# New_Project_2023-10-24_16-38-30.net
KiCad netlist of a schematic drawn in EasyEDA Pro
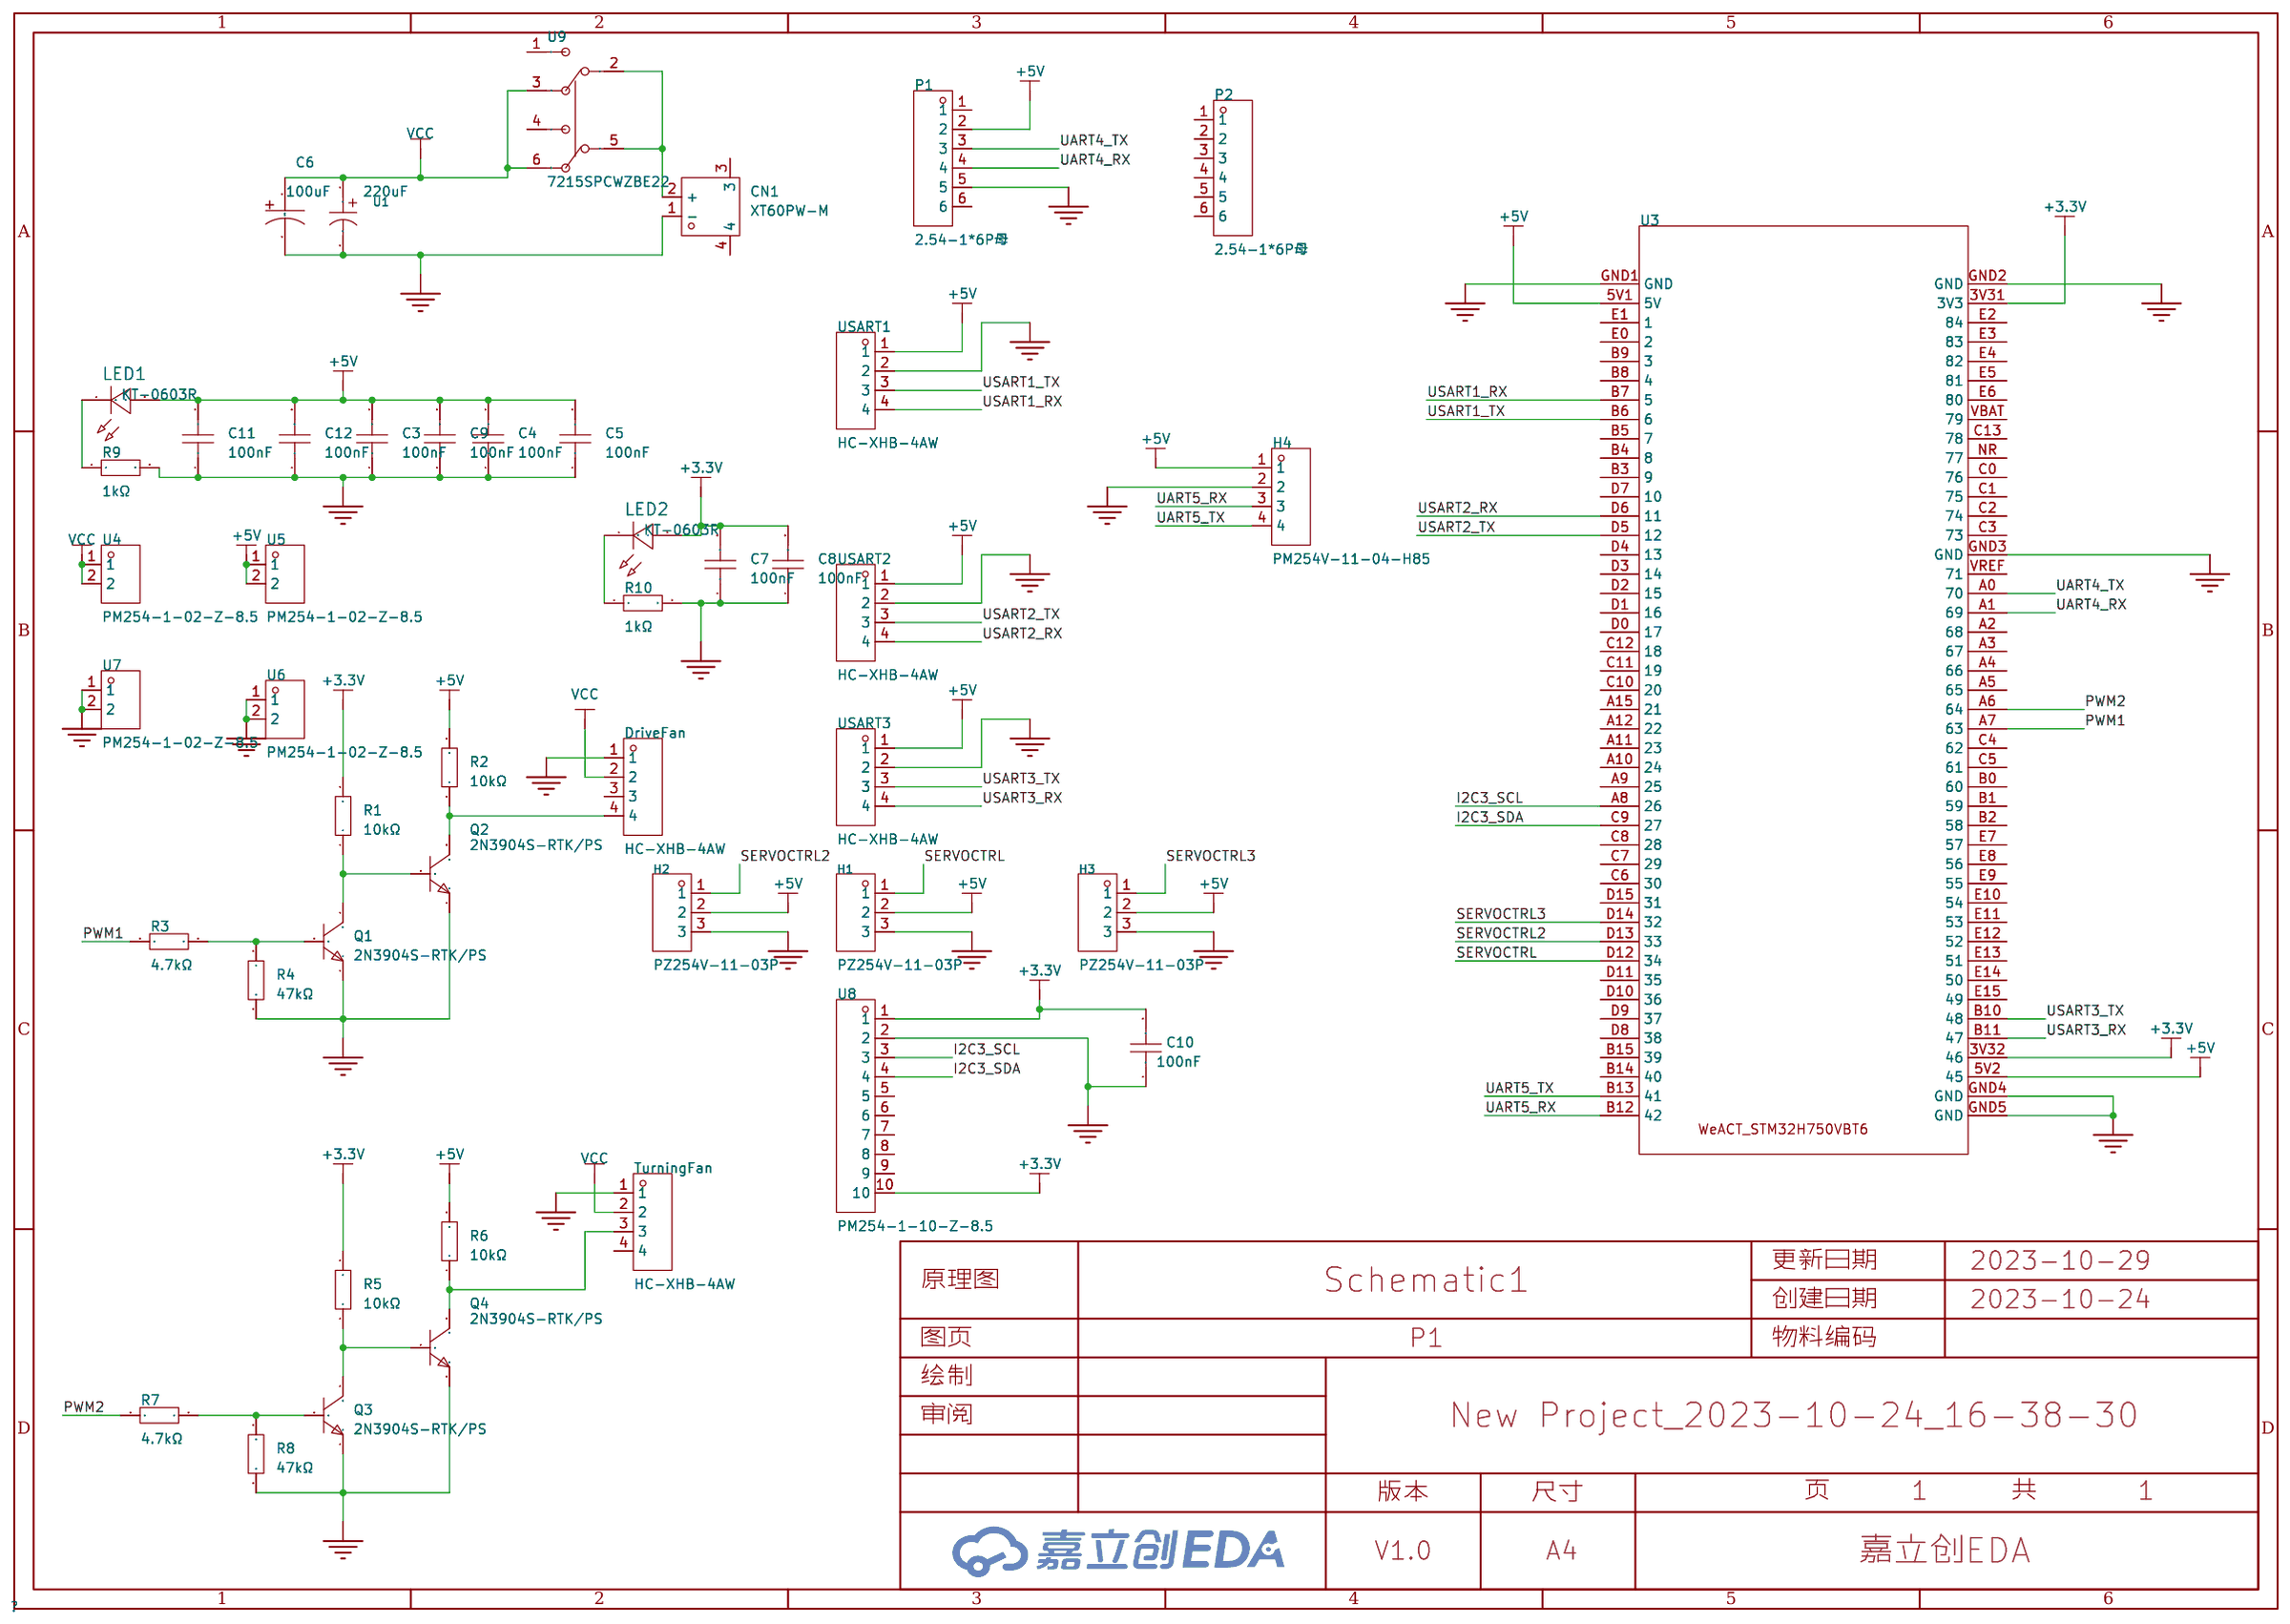
[diagram p0: schematic sheet]

(export (version "E")
  (design (tool "Eeschema 10.0.6"))
  (components
    (comp (ref "C3")
      (value "100nF")
      (footprint "easyedapro:C0603")
      (description "容值:100nF;精度:±10%;额定电压:50V;材质(温度系数):X7R;")
      (fields
        (field (name "Manufacturer Part") "CC0603KRX7R9BB104")
        (field (name "Manufacturer") "YAGEO(国巨)")
      )
      (libsource (lib "easyedapro") (part "CC0603KRX7R9BB104"))
    )
    (comp (ref "C4")
      (value "100nF")
      (footprint "easyedapro:C0603")
      (description "容值:100nF;精度:±10%;额定电压:50V;材质(温度系数):X7R;")
      (fields
        (field (name "Manufacturer Part") "CC0603KRX7R9BB104")
        (field (name "Manufacturer") "YAGEO(国巨)")
      )
      (libsource (lib "easyedapro") (part "CC0603KRX7R9BB104"))
    )
    (comp (ref "C5")
      (value "100nF")
      (footprint "easyedapro:C0603")
      (description "容值:100nF;精度:±10%;额定电压:50V;材质(温度系数):X7R;")
      (fields
        (field (name "Manufacturer Part") "CC0603KRX7R9BB104")
        (field (name "Manufacturer") "YAGEO(国巨)")
      )
      (libsource (lib "easyedapro") (part "CC0603KRX7R9BB104"))
    )
    (comp (ref "C6")
      (value "100uF")
      (footprint "easyedapro:CAP-SMD_BD6.3-L6.6-W6.6-RD")
      (description "容值:100uF;精度:±20%;额定电压:25V;纹波电流:-;等效串联电阻:-;")
      (fields (field (name "Manufacturer Part") "VZH101M1ETR-0607") (field (name "Manufacturer") "lelon(立隆)"))
      (libsource (lib "easyedapro") (part "VZH101M1ETR-0607"))
    )
    (comp (ref "C7")
      (value "100nF")
      (footprint "easyedapro:C0603")
      (description "容值:100nF;精度:±10%;额定电压:50V;材质(温度系数):X7R;")
      (fields
        (field (name "Manufacturer Part") "CC0603KRX7R9BB104")
        (field (name "Manufacturer") "YAGEO(国巨)")
      )
      (libsource (lib "easyedapro") (part "CC0603KRX7R9BB104"))
    )
    (comp (ref "C8")
      (value "100nF")
      (footprint "easyedapro:C0603")
      (description "容值:100nF;精度:±10%;额定电压:50V;材质(温度系数):X7R;")
      (fields
        (field (name "Manufacturer Part") "CC0603KRX7R9BB104")
        (field (name "Manufacturer") "YAGEO(国巨)")
      )
      (libsource (lib "easyedapro") (part "CC0603KRX7R9BB104"))
    )
    (comp (ref "C9")
      (value "100nF")
      (footprint "easyedapro:C0603")
      (description "容值:100nF;精度:±10%;额定电压:50V;材质(温度系数):X7R;")
      (fields
        (field (name "Manufacturer Part") "CC0603KRX7R9BB104")
        (field (name "Manufacturer") "YAGEO(国巨)")
      )
      (libsource (lib "easyedapro") (part "CC0603KRX7R9BB104"))
    )
    (comp (ref "C10")
      (value "100nF")
      (footprint "easyedapro:C0603")
      (description "容值:100nF;精度:±10%;额定电压:50V;材质(温度系数):X7R;")
      (fields
        (field (name "Manufacturer Part") "CC0603KRX7R9BB104")
        (field (name "Manufacturer") "YAGEO(国巨)")
      )
      (libsource (lib "easyedapro") (part "CC0603KRX7R9BB104"))
    )
    (comp (ref "C11")
      (value "100nF")
      (footprint "easyedapro:C0603")
      (description "容值:100nF;精度:±10%;额定电压:50V;材质(温度系数):X7R;")
      (fields
        (field (name "Manufacturer Part") "CC0603KRX7R9BB104")
        (field (name "Manufacturer") "YAGEO(国巨)")
      )
      (libsource (lib "easyedapro") (part "CC0603KRX7R9BB104"))
    )
    (comp (ref "C12")
      (value "100nF")
      (footprint "easyedapro:C0603")
      (description "容值:100nF;精度:±10%;额定电压:50V;材质(温度系数):X7R;")
      (fields
        (field (name "Manufacturer Part") "CC0603KRX7R9BB104")
        (field (name "Manufacturer") "YAGEO(国巨)")
      )
      (libsource (lib "easyedapro") (part "CC0603KRX7R9BB104"))
    )
    (comp (ref "CN1")
      (value "XT60PW-M")
      (footprint "easyedapro:CONN-TH_XT60PW-M")
      (description "模型锂电连接器")
      (fields (field (name "Manufacturer") "AMASS(艾迈斯)"))
      (libsource (lib "easyedapro") (part "XT60PW-M"))
    )
    (comp (ref "DriveFan")
      (value "HC-XHB-4AW")
      (footprint "easyedapro:CONN-TH_4P-P2.5_HCTL_HC-XHB-4AW")
      (description "参考系列:-;间距:2.5mm;插针结构:1x4P;排数:1;每排PIN数:4;行距:-;公母:公型插针;安装方式:弯插;额定电流:3A;工作温度范围:-25°C~+85°C;")
      (fields (field (name "Manufacturer") "HCTL(华灿天禄)"))
      (libsource (lib "easyedapro") (part "HC-XHB-4AW"))
    )
    (comp (ref "H1")
      (value "PZ254V-11-03P")
      (footprint "easyedapro:HDR-TH_3P-P2.54-V-M")
      (fields (field (name "Manufacturer") "XFCN(兴飞)"))
      (libsource (lib "easyedapro") (part "PZ254V-11-03P_C2937625"))
    )
    (comp (ref "H2")
      (value "PZ254V-11-03P")
      (footprint "easyedapro:HDR-TH_3P-P2.54-V-M")
      (fields (field (name "Manufacturer") "XFCN(兴飞)"))
      (libsource (lib "easyedapro") (part "PZ254V-11-03P_C2937625"))
    )
    (comp (ref "H3")
      (value "PZ254V-11-03P")
      (footprint "easyedapro:HDR-TH_3P-P2.54-V-M")
      (fields (field (name "Manufacturer") "XFCN(兴飞)"))
      (libsource (lib "easyedapro") (part "PZ254V-11-03P_C2937625"))
    )
    (comp (ref "H4")
      (value "PM254V-11-04-H85")
      (footprint "easyedapro:HDR-TH_4P-P2.54-V-F")
      (description "排数:单排;总孔位数:4P;间距:2.54mm;插孔结构:1x4P;行距:-;安装类型:直插;塑高:-;触头材质:黄铜;触头镀层:-;")
      (fields (field (name "Manufacturer") "XFCN(兴飞)"))
      (libsource (lib "easyedapro") (part "PM254V-11-04-H85"))
    )
    (comp (ref "LED1")
      (value "KT-0603R")
      (footprint "easyedapro:LED_0603")
      (fields (field (name "Manufacturer") "KENTO"))
      (libsource (lib "easyedapro") (part "LED_R"))
    )
    (comp (ref "LED2")
      (value "KT-0603R")
      (footprint "easyedapro:LED_0603")
      (fields (field (name "Manufacturer") "KENTO"))
      (libsource (lib "easyedapro") (part "LED_R"))
    )
    (comp (ref "P1")
      (value "2.54-1*6P母")
      (footprint "easyedapro:HDR-TH_6P-P2.54-V-F")
      (description "排数:单排;总孔位数:6P;间距:2.54mm;插孔结构:1x6P;行距:-;安装类型:直插;塑高:-;触头材质:-;触头镀层:-;")
      (fields (field (name "Manufacturer") "BOOMELE(博穆精密)"))
      (libsource (lib "easyedapro") (part "Header-Female-2.54_1x6"))
    )
    (comp (ref "P2")
      (value "2.54-1*6P母")
      (footprint "easyedapro:HDR-TH_6P-P2.54-V-F")
      (description "排数:单排;总孔位数:6P;间距:2.54mm;插孔结构:1x6P;行距:-;安装类型:直插;塑高:-;触头材质:-;触头镀层:-;")
      (fields (field (name "Manufacturer") "BOOMELE(博穆精密)"))
      (libsource (lib "easyedapro") (part "Header-Female-2.54_1x6"))
    )
    (comp (ref "Q1")
      (value "2N3904S-RTK/PS")
      (footprint "easyedapro:SOT-23-3_L2.9-W1.3-P1.90-LS2.4-TR")
      (description "晶体管类型:NPN;集射极击穿电压(Vceo):40V;集电极电流(Ic):200mA;功率(Pd):350mW;直流电流增益(hFE@Ic,Vce):100@10mA,1V;")
      (fields (field (name "Manufacturer") "KEC"))
      (libsource (lib "easyedapro") (part "2n3904S-RTK/PS_C18536"))
    )
    (comp (ref "Q2")
      (value "2N3904S-RTK/PS")
      (footprint "easyedapro:SOT-23-3_L2.9-W1.3-P1.90-LS2.4-TR")
      (description "晶体管类型:NPN;集射极击穿电压(Vceo):40V;集电极电流(Ic):200mA;功率(Pd):350mW;直流电流增益(hFE@Ic,Vce):100@10mA,1V;")
      (fields (field (name "Manufacturer") "KEC"))
      (libsource (lib "easyedapro") (part "2n3904S-RTK/PS_C18536"))
    )
    (comp (ref "Q3")
      (value "2N3904S-RTK/PS")
      (footprint "easyedapro:SOT-23-3_L2.9-W1.3-P1.90-LS2.4-TR")
      (description "晶体管类型:NPN;集射极击穿电压(Vceo):40V;集电极电流(Ic):200mA;功率(Pd):350mW;直流电流增益(hFE@Ic,Vce):100@10mA,1V;")
      (fields (field (name "Manufacturer") "KEC"))
      (libsource (lib "easyedapro") (part "2n3904S-RTK/PS_C18536"))
    )
    (comp (ref "Q4")
      (value "2N3904S-RTK/PS")
      (footprint "easyedapro:SOT-23-3_L2.9-W1.3-P1.90-LS2.4-TR")
      (description "晶体管类型:NPN;集射极击穿电压(Vceo):40V;集电极电流(Ic):200mA;功率(Pd):350mW;直流电流增益(hFE@Ic,Vce):100@10mA,1V;")
      (fields (field (name "Manufacturer") "KEC"))
      (libsource (lib "easyedapro") (part "2n3904S-RTK/PS_C18536"))
    )
    (comp (ref "R1")
      (value "10kΩ")
      (footprint "easyedapro:R0603")
      (fields
        (field (name "Manufacturer Part") "0603WAF1002T5E")
        (field (name "Manufacturer") "UNI-ROYAL(厚声)")
      )
      (libsource (lib "easyedapro") (part "电阻"))
    )
    (comp (ref "R2")
      (value "10kΩ")
      (footprint "easyedapro:R0603")
      (fields
        (field (name "Manufacturer Part") "0603WAF1002T5E")
        (field (name "Manufacturer") "UNI-ROYAL(厚声)")
      )
      (libsource (lib "easyedapro") (part "电阻"))
    )
    (comp (ref "R3")
      (value "4.7kΩ")
      (footprint "easyedapro:R0603")
      (fields
        (field (name "Manufacturer Part") "0603WAF4701T5E")
        (field (name "Manufacturer") "UNI-ROYAL(厚声)")
      )
      (libsource (lib "easyedapro") (part "电阻"))
    )
    (comp (ref "R4")
      (value "47kΩ")
      (footprint "easyedapro:R0603")
      (fields
        (field (name "Manufacturer Part") "0603WAF4702T5E")
        (field (name "Manufacturer") "UNI-ROYAL(厚声)")
      )
      (libsource (lib "easyedapro") (part "电阻"))
    )
    (comp (ref "R5")
      (value "10kΩ")
      (footprint "easyedapro:R0603")
      (fields
        (field (name "Manufacturer Part") "0603WAF1002T5E")
        (field (name "Manufacturer") "UNI-ROYAL(厚声)")
      )
      (libsource (lib "easyedapro") (part "电阻"))
    )
    (comp (ref "R6")
      (value "10kΩ")
      (footprint "easyedapro:R0603")
      (fields
        (field (name "Manufacturer Part") "0603WAF1002T5E")
        (field (name "Manufacturer") "UNI-ROYAL(厚声)")
      )
      (libsource (lib "easyedapro") (part "电阻"))
    )
    (comp (ref "R7")
      (value "4.7kΩ")
      (footprint "easyedapro:R0603")
      (fields
        (field (name "Manufacturer Part") "0603WAF4701T5E")
        (field (name "Manufacturer") "UNI-ROYAL(厚声)")
      )
      (libsource (lib "easyedapro") (part "电阻"))
    )
    (comp (ref "R8")
      (value "47kΩ")
      (footprint "easyedapro:R0603")
      (fields
        (field (name "Manufacturer Part") "0603WAF4702T5E")
        (field (name "Manufacturer") "UNI-ROYAL(厚声)")
      )
      (libsource (lib "easyedapro") (part "电阻"))
    )
    (comp (ref "R9")
      (value "1kΩ")
      (footprint "easyedapro:R0603")
      (fields
        (field (name "Manufacturer Part") "0603WAF1001T5E")
        (field (name "Manufacturer") "UNI-ROYAL(厚声)")
      )
      (libsource (lib "easyedapro") (part "电阻"))
    )
    (comp (ref "R10")
      (value "1kΩ")
      (footprint "easyedapro:R0603")
      (fields
        (field (name "Manufacturer Part") "0603WAF1001T5E")
        (field (name "Manufacturer") "UNI-ROYAL(厚声)")
      )
      (libsource (lib "easyedapro") (part "电阻"))
    )
    (comp (ref "TurningFan")
      (value "HC-XHB-4AW")
      (footprint "easyedapro:CONN-TH_4P-P2.5_HCTL_HC-XHB-4AW")
      (description "参考系列:-;间距:2.5mm;插针结构:1x4P;排数:1;每排PIN数:4;行距:-;公母:公型插针;安装方式:弯插;额定电流:3A;工作温度范围:-25°C~+85°C;")
      (fields (field (name "Manufacturer") "HCTL(华灿天禄)"))
      (libsource (lib "easyedapro") (part "HC-XHB-4AW"))
    )
    (comp (ref "U1")
      (value "220uF")
      (footprint "easyedapro:CAP-SMD_BD6.3-L6.6-W6.6-LS7.2-FD")
      (description "容值:220uF;精度:±20%;额定电压:25V;纹波电流:165mA@120Hz;等效串联电阻:-;")
      (fields (field (name "Manufacturer Part") "RST220UF25V019") (field (name "Manufacturer") "KNSCHA(科尼盛)"))
      (libsource (lib "easyedapro") (part "RST220UF25V019"))
    )
    (comp (ref "U3")
      (value "~")
      (footprint "easyedapro:WeAct_STM32H750VBT6核心板")
      (libsource (lib "easyedapro") (part "STM32H750VBT6"))
    )
    (comp (ref "U4")
      (value "PM254-1-02-Z-8.5")
      (footprint "easyedapro:HDR-TH_2P-P2.54-V-F")
      (fields (field (name "Manufacturer") "HCTL(华灿天禄)"))
      (libsource (lib "easyedapro") (part "PM254-1-02-Z-8.5"))
    )
    (comp (ref "U5")
      (value "PM254-1-02-Z-8.5")
      (footprint "easyedapro:HDR-TH_2P-P2.54-V-F")
      (fields (field (name "Manufacturer") "HCTL(华灿天禄)"))
      (libsource (lib "easyedapro") (part "PM254-1-02-Z-8.5"))
    )
    (comp (ref "U6")
      (value "PM254-1-02-Z-8.5")
      (footprint "easyedapro:HDR-TH_2P-P2.54-V-F")
      (fields (field (name "Manufacturer") "HCTL(华灿天禄)"))
      (libsource (lib "easyedapro") (part "PM254-1-02-Z-8.5"))
    )
    (comp (ref "U7")
      (value "PM254-1-02-Z-8.5")
      (footprint "easyedapro:HDR-TH_2P-P2.54-V-F")
      (fields (field (name "Manufacturer") "HCTL(华灿天禄)"))
      (libsource (lib "easyedapro") (part "PM254-1-02-Z-8.5"))
    )
    (comp (ref "U8")
      (value "PM254-1-10-Z-8.5")
      (footprint "easyedapro:HDR-TH_10P-P2.54-V-F")
      (fields (field (name "Manufacturer") "HCTL(华灿天禄)"))
      (libsource (lib "easyedapro") (part "PM254-1-10-Z-8.5"))
    )
    (comp (ref "U9")
      (value "7215SPCWZBE22")
      (footprint "easyedapro:SW-TH_6P-L12.7-W11.4-P4.70-LS4.8")
      (fields (field (name "Manufacturer") "C&amp;K"))
      (libsource (lib "easyedapro") (part "7215SPCWZBE22"))
    )
    (comp (ref "USART1")
      (value "HC-XHB-4AW")
      (footprint "easyedapro:CONN-TH_4P-P2.5_HCTL_HC-XHB-4AW")
      (description "参考系列:-;间距:2.5mm;插针结构:1x4P;排数:1;每排PIN数:4;行距:-;公母:公型插针;安装方式:弯插;额定电流:3A;工作温度范围:-25°C~+85°C;")
      (fields (field (name "Manufacturer") "HCTL(华灿天禄)"))
      (libsource (lib "easyedapro") (part "HC-XHB-4AW"))
    )
    (comp (ref "USART2")
      (value "HC-XHB-4AW")
      (footprint "easyedapro:CONN-TH_4P-P2.5_HCTL_HC-XHB-4AW")
      (description "参考系列:-;间距:2.5mm;插针结构:1x4P;排数:1;每排PIN数:4;行距:-;公母:公型插针;安装方式:弯插;额定电流:3A;工作温度范围:-25°C~+85°C;")
      (fields (field (name "Manufacturer") "HCTL(华灿天禄)"))
      (libsource (lib "easyedapro") (part "HC-XHB-4AW"))
    )
    (comp (ref "USART3")
      (value "HC-XHB-4AW")
      (footprint "easyedapro:CONN-TH_4P-P2.5_HCTL_HC-XHB-4AW")
      (description "参考系列:-;间距:2.5mm;插针结构:1x4P;排数:1;每排PIN数:4;行距:-;公母:公型插针;安装方式:弯插;额定电流:3A;工作温度范围:-25°C~+85°C;")
      (fields (field (name "Manufacturer") "HCTL(华灿天禄)"))
      (libsource (lib "easyedapro") (part "HC-XHB-4AW"))
    )
  )
  (nets
    (net (code "1") (name "+3.3V") (class "Default")
      (node (ref "C10") (pin "2") (pinfunction "2_2") (pintype "input"))
      (node (ref "C7") (pin "2") (pinfunction "2_2") (pintype "input"))
      (node (ref "C8") (pin "2") (pinfunction "2_2") (pintype "input"))
      (node (ref "LED2") (pin "2") (pinfunction "A_2") (pintype "input"))
      (node (ref "R1") (pin "2") (pinfunction "2_2") (pintype "input"))
      (node (ref "R5") (pin "2") (pinfunction "2_2") (pintype "input"))
      (node (ref "U3") (pin "3V31") (pinfunction "3V3_3V31") (pintype "input"))
      (node (ref "U3") (pin "3V32") (pinfunction "46_3V32") (pintype "input"))
      (node (ref "U8") (pin "1") (pinfunction "1_1") (pintype "unspecified"))
      (node (ref "U8") (pin "10") (pinfunction "10_10") (pintype "unspecified"))
    )
    (net (code "2") (name "+5V") (class "Default")
      (node (ref "C11") (pin "2") (pinfunction "2_2") (pintype "input"))
      (node (ref "C12") (pin "2") (pinfunction "2_2") (pintype "input"))
      (node (ref "C3") (pin "2") (pinfunction "2_2") (pintype "input"))
      (node (ref "C4") (pin "2") (pinfunction "2_2") (pintype "input"))
      (node (ref "C5") (pin "2") (pinfunction "2_2") (pintype "input"))
      (node (ref "C9") (pin "2") (pinfunction "2_2") (pintype "input"))
      (node (ref "H1") (pin "2") (pinfunction "2_2") (pintype "input"))
      (node (ref "H2") (pin "2") (pinfunction "2_2") (pintype "input"))
      (node (ref "H3") (pin "2") (pinfunction "2_2") (pintype "input"))
      (node (ref "H4") (pin "1") (pinfunction "1_1") (pintype "unspecified"))
      (node (ref "LED1") (pin "2") (pinfunction "A_2") (pintype "input"))
      (node (ref "P1") (pin "2") (pinfunction "2_2") (pintype "unspecified"))
      (node (ref "R2") (pin "2") (pinfunction "2_2") (pintype "input"))
      (node (ref "R6") (pin "2") (pinfunction "2_2") (pintype "input"))
      (node (ref "U3") (pin "5V1") (pinfunction "5V_5V1") (pintype "input"))
      (node (ref "U3") (pin "5V2") (pinfunction "45_5V2") (pintype "input"))
      (node (ref "U5") (pin "1") (pinfunction "1_1") (pintype "unspecified"))
      (node (ref "U5") (pin "2") (pinfunction "2_2") (pintype "unspecified"))
      (node (ref "USART1") (pin "1") (pinfunction "1_1") (pintype "input"))
      (node (ref "USART2") (pin "1") (pinfunction "1_1") (pintype "input"))
      (node (ref "USART3") (pin "1") (pinfunction "1_1") (pintype "input"))
    )
    (net (code "3") (name "/I2C3_SCL") (class "Default")
      (node (ref "U3") (pin "A8") (pinfunction "26_A8") (pintype "input"))
      (node (ref "U8") (pin "3") (pinfunction "3_3") (pintype "unspecified"))
    )
    (net (code "4") (name "/I2C3_SDA") (class "Default")
      (node (ref "U3") (pin "C9") (pinfunction "27_C9") (pintype "input"))
      (node (ref "U8") (pin "4") (pinfunction "4_4") (pintype "unspecified"))
    )
    (net (code "5") (name "/PWM1") (class "Default")
      (node (ref "R3") (pin "2") (pinfunction "2_2") (pintype "input"))
      (node (ref "U3") (pin "A7") (pinfunction "63_A7") (pintype "input"))
    )
    (net (code "6") (name "/PWM2") (class "Default")
      (node (ref "R7") (pin "2") (pinfunction "2_2") (pintype "input"))
      (node (ref "U3") (pin "A6") (pinfunction "64_A6") (pintype "input"))
    )
    (net (code "7") (name "/SERVOCTRL") (class "Default")
      (node (ref "H1") (pin "1") (pinfunction "1_1") (pintype "input"))
      (node (ref "U3") (pin "D12") (pinfunction "34_D12") (pintype "input"))
    )
    (net (code "8") (name "/SERVOCTRL2") (class "Default")
      (node (ref "H2") (pin "1") (pinfunction "1_1") (pintype "input"))
      (node (ref "U3") (pin "D13") (pinfunction "33_D13") (pintype "input"))
    )
    (net (code "9") (name "/SERVOCTRL3") (class "Default")
      (node (ref "H3") (pin "1") (pinfunction "1_1") (pintype "input"))
      (node (ref "U3") (pin "D14") (pinfunction "32_D14") (pintype "input"))
    )
    (net (code "10") (name "/UART4_RX") (class "Default")
      (node (ref "P1") (pin "4") (pinfunction "4_4") (pintype "unspecified"))
      (node (ref "U3") (pin "A1") (pinfunction "69_A1") (pintype "input"))
    )
    (net (code "11") (name "/UART4_TX") (class "Default")
      (node (ref "P1") (pin "3") (pinfunction "3_3") (pintype "unspecified"))
      (node (ref "U3") (pin "A0") (pinfunction "70_A0") (pintype "input"))
    )
    (net (code "12") (name "/UART5_RX") (class "Default")
      (node (ref "H4") (pin "3") (pinfunction "3_3") (pintype "unspecified"))
      (node (ref "U3") (pin "B12") (pinfunction "42_B12") (pintype "input"))
    )
    (net (code "13") (name "/UART5_TX") (class "Default")
      (node (ref "H4") (pin "4") (pinfunction "4_4") (pintype "unspecified"))
      (node (ref "U3") (pin "B13") (pinfunction "41_B13") (pintype "input"))
    )
    (net (code "14") (name "/USART1_RX") (class "Default")
      (node (ref "U3") (pin "B7") (pinfunction "5_B7") (pintype "input"))
      (node (ref "USART1") (pin "4") (pinfunction "4_4") (pintype "input"))
    )
    (net (code "15") (name "/USART1_TX") (class "Default")
      (node (ref "U3") (pin "B6") (pinfunction "6_B6") (pintype "input"))
      (node (ref "USART1") (pin "3") (pinfunction "3_3") (pintype "input"))
    )
    (net (code "16") (name "/USART2_RX") (class "Default")
      (node (ref "U3") (pin "D6") (pinfunction "11_D6") (pintype "input"))
      (node (ref "USART2") (pin "4") (pinfunction "4_4") (pintype "input"))
    )
    (net (code "17") (name "/USART2_TX") (class "Default")
      (node (ref "U3") (pin "D5") (pinfunction "12_D5") (pintype "input"))
      (node (ref "USART2") (pin "3") (pinfunction "3_3") (pintype "input"))
    )
    (net (code "18") (name "/USART3_RX") (class "Default")
      (node (ref "U3") (pin "B11") (pinfunction "47_B11") (pintype "input"))
      (node (ref "USART3") (pin "4") (pinfunction "4_4") (pintype "input"))
    )
    (net (code "19") (name "/USART3_TX") (class "Default")
      (node (ref "U3") (pin "B10") (pinfunction "48_B10") (pintype "input"))
      (node (ref "USART3") (pin "3") (pinfunction "3_3") (pintype "input"))
    )
    (net (code "20") (name "GND") (class "Default")
      (node (ref "C10") (pin "1") (pinfunction "1_1") (pintype "input"))
      (node (ref "C11") (pin "1") (pinfunction "1_1") (pintype "input"))
      (node (ref "C12") (pin "1") (pinfunction "1_1") (pintype "input"))
      (node (ref "C3") (pin "1") (pinfunction "1_1") (pintype "input"))
      (node (ref "C4") (pin "1") (pinfunction "1_1") (pintype "input"))
      (node (ref "C5") (pin "1") (pinfunction "1_1") (pintype "input"))
      (node (ref "C6") (pin "2") (pinfunction "2_2") (pintype "input"))
      (node (ref "C7") (pin "1") (pinfunction "1_1") (pintype "input"))
      (node (ref "C8") (pin "1") (pinfunction "1_1") (pintype "input"))
      (node (ref "C9") (pin "1") (pinfunction "1_1") (pintype "input"))
      (node (ref "CN1") (pin "1") (pinfunction "-_1") (pintype "input"))
      (node (ref "DriveFan") (pin "1") (pinfunction "1_1") (pintype "input"))
      (node (ref "H1") (pin "3") (pinfunction "3_3") (pintype "input"))
      (node (ref "H2") (pin "3") (pinfunction "3_3") (pintype "input"))
      (node (ref "H3") (pin "3") (pinfunction "3_3") (pintype "input"))
      (node (ref "H4") (pin "2") (pinfunction "2_2") (pintype "unspecified"))
      (node (ref "P1") (pin "5") (pinfunction "5_5") (pintype "unspecified"))
      (node (ref "Q1") (pin "1") (pinfunction "E_1") (pintype "input"))
      (node (ref "Q2") (pin "1") (pinfunction "E_1") (pintype "input"))
      (node (ref "Q3") (pin "1") (pinfunction "E_1") (pintype "input"))
      (node (ref "Q4") (pin "1") (pinfunction "E_1") (pintype "input"))
      (node (ref "R10") (pin "2") (pinfunction "2_2") (pintype "input"))
      (node (ref "R4") (pin "2") (pinfunction "2_2") (pintype "input"))
      (node (ref "R8") (pin "2") (pinfunction "2_2") (pintype "input"))
      (node (ref "R9") (pin "2") (pinfunction "2_2") (pintype "input"))
      (node (ref "TurningFan") (pin "1") (pinfunction "1_1") (pintype "input"))
      (node (ref "U1") (pin "2") (pinfunction "2_2") (pintype "input"))
      (node (ref "U3") (pin "GND1") (pinfunction "GND_GND1") (pintype "input"))
      (node (ref "U3") (pin "GND2") (pinfunction "GND_GND2") (pintype "input"))
      (node (ref "U3") (pin "GND3") (pinfunction "GND_GND3") (pintype "input"))
      (node (ref "U3") (pin "GND4") (pinfunction "GND_GND4") (pintype "input"))
      (node (ref "U3") (pin "GND5") (pinfunction "GND_GND5") (pintype "input"))
      (node (ref "U6") (pin "1") (pinfunction "1_1") (pintype "unspecified"))
      (node (ref "U6") (pin "2") (pinfunction "2_2") (pintype "unspecified"))
      (node (ref "U7") (pin "1") (pinfunction "1_1") (pintype "unspecified"))
      (node (ref "U7") (pin "2") (pinfunction "2_2") (pintype "unspecified"))
      (node (ref "U8") (pin "2") (pinfunction "2_2") (pintype "unspecified"))
      (node (ref "USART1") (pin "2") (pinfunction "2_2") (pintype "input"))
      (node (ref "USART2") (pin "2") (pinfunction "2_2") (pintype "input"))
      (node (ref "USART3") (pin "2") (pinfunction "2_2") (pintype "input"))
    )
    (net (code "21") (name "Net-(CN1-+)") (class "Default")
      (node (ref "CN1") (pin "2") (pinfunction "+_2") (pintype "input"))
      (node (ref "U9") (pin "2") (pinfunction "2_2") (pintype "input"))
      (node (ref "U9") (pin "5") (pinfunction "5_5") (pintype "input"))
    )
    (net (code "22") (name "Net-(LED1-C)") (class "Default")
      (node (ref "LED1") (pin "1") (pinfunction "C_1") (pintype "input"))
      (node (ref "R9") (pin "1") (pinfunction "1_1") (pintype "input"))
    )
    (net (code "23") (name "Net-(LED2-C)") (class "Default")
      (node (ref "LED2") (pin "1") (pinfunction "C_1") (pintype "input"))
      (node (ref "R10") (pin "1") (pinfunction "1_1") (pintype "input"))
    )
    (net (code "24") (name "Net-(Q1-B)") (class "Default")
      (node (ref "Q1") (pin "2") (pinfunction "B_2") (pintype "input"))
      (node (ref "R3") (pin "1") (pinfunction "1_1") (pintype "input"))
      (node (ref "R4") (pin "1") (pinfunction "1_1") (pintype "input"))
    )
    (net (code "25") (name "Net-(Q1-C)") (class "Default")
      (node (ref "Q1") (pin "3") (pinfunction "C_3") (pintype "input"))
      (node (ref "Q2") (pin "2") (pinfunction "B_2") (pintype "input"))
      (node (ref "R1") (pin "1") (pinfunction "1_1") (pintype "input"))
    )
    (net (code "26") (name "Net-(Q2-C)") (class "Default")
      (node (ref "DriveFan") (pin "4") (pinfunction "4_4") (pintype "input"))
      (node (ref "Q2") (pin "3") (pinfunction "C_3") (pintype "input"))
      (node (ref "R2") (pin "1") (pinfunction "1_1") (pintype "input"))
    )
    (net (code "27") (name "Net-(Q3-B)") (class "Default")
      (node (ref "Q3") (pin "2") (pinfunction "B_2") (pintype "input"))
      (node (ref "R7") (pin "1") (pinfunction "1_1") (pintype "input"))
      (node (ref "R8") (pin "1") (pinfunction "1_1") (pintype "input"))
    )
    (net (code "28") (name "Net-(Q3-C)") (class "Default")
      (node (ref "Q3") (pin "3") (pinfunction "C_3") (pintype "input"))
      (node (ref "Q4") (pin "2") (pinfunction "B_2") (pintype "input"))
      (node (ref "R5") (pin "1") (pinfunction "1_1") (pintype "input"))
    )
    (net (code "29") (name "Net-(Q4-C)") (class "Default")
      (node (ref "Q4") (pin "3") (pinfunction "C_3") (pintype "input"))
      (node (ref "R6") (pin "1") (pinfunction "1_1") (pintype "input"))
      (node (ref "TurningFan") (pin "3") (pinfunction "3_3") (pintype "input"))
    )
    (net (code "30") (name "VCC") (class "Default")
      (node (ref "C6") (pin "1") (pinfunction "1_1") (pintype "input"))
      (node (ref "DriveFan") (pin "2") (pinfunction "2_2") (pintype "input"))
      (node (ref "TurningFan") (pin "2") (pinfunction "2_2") (pintype "input"))
      (node (ref "U1") (pin "1") (pinfunction "1_1") (pintype "input"))
      (node (ref "U4") (pin "1") (pinfunction "1_1") (pintype "unspecified"))
      (node (ref "U4") (pin "2") (pinfunction "2_2") (pintype "unspecified"))
      (node (ref "U9") (pin "3") (pinfunction "3_3") (pintype "input"))
      (node (ref "U9") (pin "6") (pinfunction "6_6") (pintype "input"))
    )
    (net (code "31") (name "unconnected-(CN1-Pad3)") (class "Default")
      (node (ref "CN1") (pin "3") (pinfunction "3_3") (pintype "input"))
    )
    (net (code "32") (name "unconnected-(CN1-Pad4)") (class "Default")
      (node (ref "CN1") (pin "4") (pinfunction "4_4") (pintype "input"))
    )
    (net (code "33") (name "unconnected-(DriveFan-Pad3)") (class "Default")
      (node (ref "DriveFan") (pin "3") (pinfunction "3_3") (pintype "input"))
    )
    (net (code "34") (name "unconnected-(P1-Pad1)") (class "Default")
      (node (ref "P1") (pin "1") (pinfunction "1_1") (pintype "unspecified"))
    )
    (net (code "35") (name "unconnected-(P1-Pad6)") (class "Default")
      (node (ref "P1") (pin "6") (pinfunction "6_6") (pintype "unspecified"))
    )
    (net (code "36") (name "unconnected-(P2-Pad1)") (class "Default")
      (node (ref "P2") (pin "1") (pinfunction "1_1") (pintype "unspecified"))
    )
    (net (code "37") (name "unconnected-(P2-Pad2)") (class "Default")
      (node (ref "P2") (pin "2") (pinfunction "2_2") (pintype "unspecified"))
    )
    (net (code "38") (name "unconnected-(P2-Pad3)") (class "Default")
      (node (ref "P2") (pin "3") (pinfunction "3_3") (pintype "unspecified"))
    )
    (net (code "39") (name "unconnected-(P2-Pad4)") (class "Default")
      (node (ref "P2") (pin "4") (pinfunction "4_4") (pintype "unspecified"))
    )
    (net (code "40") (name "unconnected-(P2-Pad5)") (class "Default")
      (node (ref "P2") (pin "5") (pinfunction "5_5") (pintype "unspecified"))
    )
    (net (code "41") (name "unconnected-(P2-Pad6)") (class "Default")
      (node (ref "P2") (pin "6") (pinfunction "6_6") (pintype "unspecified"))
    )
    (net (code "42") (name "unconnected-(TurningFan-Pad4)") (class "Default")
      (node (ref "TurningFan") (pin "4") (pinfunction "4_4") (pintype "input"))
    )
    (net (code "43") (name "unconnected-(U3-1-PadE1)") (class "Default")
      (node (ref "U3") (pin "E1") (pinfunction "1_E1") (pintype "input"))
    )
    (net (code "44") (name "unconnected-(U3-2-PadE0)") (class "Default")
      (node (ref "U3") (pin "E0") (pinfunction "2_E0") (pintype "input"))
    )
    (net (code "45") (name "unconnected-(U3-3-PadB9)") (class "Default")
      (node (ref "U3") (pin "B9") (pinfunction "3_B9") (pintype "input"))
    )
    (net (code "46") (name "unconnected-(U3-4-PadB8)") (class "Default")
      (node (ref "U3") (pin "B8") (pinfunction "4_B8") (pintype "input"))
    )
    (net (code "47") (name "unconnected-(U3-7-PadB5)") (class "Default")
      (node (ref "U3") (pin "B5") (pinfunction "7_B5") (pintype "input"))
    )
    (net (code "48") (name "unconnected-(U3-8-PadB4)") (class "Default")
      (node (ref "U3") (pin "B4") (pinfunction "8_B4") (pintype "input"))
    )
    (net (code "49") (name "unconnected-(U3-9-PadB3)") (class "Default")
      (node (ref "U3") (pin "B3") (pinfunction "9_B3") (pintype "input"))
    )
    (net (code "50") (name "unconnected-(U3-10-PadD7)") (class "Default")
      (node (ref "U3") (pin "D7") (pinfunction "10_D7") (pintype "input"))
    )
    (net (code "51") (name "unconnected-(U3-13-PadD4)") (class "Default")
      (node (ref "U3") (pin "D4") (pinfunction "13_D4") (pintype "input"))
    )
    (net (code "52") (name "unconnected-(U3-14-PadD3)") (class "Default")
      (node (ref "U3") (pin "D3") (pinfunction "14_D3") (pintype "input"))
    )
    (net (code "53") (name "unconnected-(U3-15-PadD2)") (class "Default")
      (node (ref "U3") (pin "D2") (pinfunction "15_D2") (pintype "input"))
    )
    (net (code "54") (name "unconnected-(U3-16-PadD1)") (class "Default")
      (node (ref "U3") (pin "D1") (pinfunction "16_D1") (pintype "input"))
    )
    (net (code "55") (name "unconnected-(U3-17-PadD0)") (class "Default")
      (node (ref "U3") (pin "D0") (pinfunction "17_D0") (pintype "input"))
    )
    (net (code "56") (name "unconnected-(U3-18-PadC12)") (class "Default")
      (node (ref "U3") (pin "C12") (pinfunction "18_C12") (pintype "input"))
    )
    (net (code "57") (name "unconnected-(U3-19-PadC11)") (class "Default")
      (node (ref "U3") (pin "C11") (pinfunction "19_C11") (pintype "input"))
    )
    (net (code "58") (name "unconnected-(U3-20-PadC10)") (class "Default")
      (node (ref "U3") (pin "C10") (pinfunction "20_C10") (pintype "input"))
    )
    (net (code "59") (name "unconnected-(U3-21-PadA15)") (class "Default")
      (node (ref "U3") (pin "A15") (pinfunction "21_A15") (pintype "input"))
    )
    (net (code "60") (name "unconnected-(U3-22-PadA12)") (class "Default")
      (node (ref "U3") (pin "A12") (pinfunction "22_A12") (pintype "input"))
    )
    (net (code "61") (name "unconnected-(U3-23-PadA11)") (class "Default")
      (node (ref "U3") (pin "A11") (pinfunction "23_A11") (pintype "input"))
    )
    (net (code "62") (name "unconnected-(U3-24-PadA10)") (class "Default")
      (node (ref "U3") (pin "A10") (pinfunction "24_A10") (pintype "input"))
    )
    (net (code "63") (name "unconnected-(U3-25-PadA9)") (class "Default")
      (node (ref "U3") (pin "A9") (pinfunction "25_A9") (pintype "input"))
    )
    (net (code "64") (name "unconnected-(U3-28-PadC8)") (class "Default")
      (node (ref "U3") (pin "C8") (pinfunction "28_C8") (pintype "input"))
    )
    (net (code "65") (name "unconnected-(U3-29-PadC7)") (class "Default")
      (node (ref "U3") (pin "C7") (pinfunction "29_C7") (pintype "input"))
    )
    (net (code "66") (name "unconnected-(U3-30-PadC6)") (class "Default")
      (node (ref "U3") (pin "C6") (pinfunction "30_C6") (pintype "input"))
    )
    (net (code "67") (name "unconnected-(U3-31-PadD15)") (class "Default")
      (node (ref "U3") (pin "D15") (pinfunction "31_D15") (pintype "input"))
    )
    (net (code "68") (name "unconnected-(U3-35-PadD11)") (class "Default")
      (node (ref "U3") (pin "D11") (pinfunction "35_D11") (pintype "input"))
    )
    (net (code "69") (name "unconnected-(U3-36-PadD10)") (class "Default")
      (node (ref "U3") (pin "D10") (pinfunction "36_D10") (pintype "input"))
    )
    (net (code "70") (name "unconnected-(U3-37-PadD9)") (class "Default")
      (node (ref "U3") (pin "D9") (pinfunction "37_D9") (pintype "input"))
    )
    (net (code "71") (name "unconnected-(U3-38-PadD8)") (class "Default")
      (node (ref "U3") (pin "D8") (pinfunction "38_D8") (pintype "input"))
    )
    (net (code "72") (name "unconnected-(U3-39-PadB15)") (class "Default")
      (node (ref "U3") (pin "B15") (pinfunction "39_B15") (pintype "input"))
    )
    (net (code "73") (name "unconnected-(U3-40-PadB14)") (class "Default")
      (node (ref "U3") (pin "B14") (pinfunction "40_B14") (pintype "input"))
    )
    (net (code "74") (name "unconnected-(U3-49-PadE15)") (class "Default")
      (node (ref "U3") (pin "E15") (pinfunction "49_E15") (pintype "input"))
    )
    (net (code "75") (name "unconnected-(U3-50-PadE14)") (class "Default")
      (node (ref "U3") (pin "E14") (pinfunction "50_E14") (pintype "input"))
    )
    (net (code "76") (name "unconnected-(U3-51-PadE13)") (class "Default")
      (node (ref "U3") (pin "E13") (pinfunction "51_E13") (pintype "input"))
    )
    (net (code "77") (name "unconnected-(U3-52-PadE12)") (class "Default")
      (node (ref "U3") (pin "E12") (pinfunction "52_E12") (pintype "input"))
    )
    (net (code "78") (name "unconnected-(U3-53-PadE11)") (class "Default")
      (node (ref "U3") (pin "E11") (pinfunction "53_E11") (pintype "input"))
    )
    (net (code "79") (name "unconnected-(U3-54-PadE10)") (class "Default")
      (node (ref "U3") (pin "E10") (pinfunction "54_E10") (pintype "input"))
    )
    (net (code "80") (name "unconnected-(U3-55-PadE9)") (class "Default")
      (node (ref "U3") (pin "E9") (pinfunction "55_E9") (pintype "input"))
    )
    (net (code "81") (name "unconnected-(U3-56-PadE8)") (class "Default")
      (node (ref "U3") (pin "E8") (pinfunction "56_E8") (pintype "input"))
    )
    (net (code "82") (name "unconnected-(U3-57-PadE7)") (class "Default")
      (node (ref "U3") (pin "E7") (pinfunction "57_E7") (pintype "input"))
    )
    (net (code "83") (name "unconnected-(U3-58-PadB2)") (class "Default")
      (node (ref "U3") (pin "B2") (pinfunction "58_B2") (pintype "input"))
    )
    (net (code "84") (name "unconnected-(U3-59-PadB1)") (class "Default")
      (node (ref "U3") (pin "B1") (pinfunction "59_B1") (pintype "input"))
    )
    (net (code "85") (name "unconnected-(U3-60-PadB0)") (class "Default")
      (node (ref "U3") (pin "B0") (pinfunction "60_B0") (pintype "input"))
    )
    (net (code "86") (name "unconnected-(U3-61-PadC5)") (class "Default")
      (node (ref "U3") (pin "C5") (pinfunction "61_C5") (pintype "input"))
    )
    (net (code "87") (name "unconnected-(U3-62-PadC4)") (class "Default")
      (node (ref "U3") (pin "C4") (pinfunction "62_C4") (pintype "input"))
    )
    (net (code "88") (name "unconnected-(U3-65-PadA5)") (class "Default")
      (node (ref "U3") (pin "A5") (pinfunction "65_A5") (pintype "input"))
    )
    (net (code "89") (name "unconnected-(U3-66-PadA4)") (class "Default")
      (node (ref "U3") (pin "A4") (pinfunction "66_A4") (pintype "input"))
    )
    (net (code "90") (name "unconnected-(U3-67-PadA3)") (class "Default")
      (node (ref "U3") (pin "A3") (pinfunction "67_A3") (pintype "input"))
    )
    (net (code "91") (name "unconnected-(U3-68-PadA2)") (class "Default")
      (node (ref "U3") (pin "A2") (pinfunction "68_A2") (pintype "input"))
    )
    (net (code "92") (name "unconnected-(U3-71-PadVREF)") (class "Default")
      (node (ref "U3") (pin "VREF") (pinfunction "71_VREF") (pintype "input"))
    )
    (net (code "93") (name "unconnected-(U3-73-PadC3)") (class "Default")
      (node (ref "U3") (pin "C3") (pinfunction "73_C3") (pintype "input"))
    )
    (net (code "94") (name "unconnected-(U3-74-PadC2)") (class "Default")
      (node (ref "U3") (pin "C2") (pinfunction "74_C2") (pintype "input"))
    )
    (net (code "95") (name "unconnected-(U3-75-PadC1)") (class "Default")
      (node (ref "U3") (pin "C1") (pinfunction "75_C1") (pintype "input"))
    )
    (net (code "96") (name "unconnected-(U3-76-PadC0)") (class "Default")
      (node (ref "U3") (pin "C0") (pinfunction "76_C0") (pintype "input"))
    )
    (net (code "97") (name "unconnected-(U3-77-PadNR)") (class "Default")
      (node (ref "U3") (pin "NR") (pinfunction "77_NR") (pintype "input"))
    )
    (net (code "98") (name "unconnected-(U3-78-PadC13)") (class "Default")
      (node (ref "U3") (pin "C13") (pinfunction "78_C13") (pintype "input"))
    )
    (net (code "99") (name "unconnected-(U3-79-PadVBAT)") (class "Default")
      (node (ref "U3") (pin "VBAT") (pinfunction "79_VBAT") (pintype "input"))
    )
    (net (code "100") (name "unconnected-(U3-80-PadE6)") (class "Default")
      (node (ref "U3") (pin "E6") (pinfunction "80_E6") (pintype "input"))
    )
    (net (code "101") (name "unconnected-(U3-81-PadE5)") (class "Default")
      (node (ref "U3") (pin "E5") (pinfunction "81_E5") (pintype "input"))
    )
    (net (code "102") (name "unconnected-(U3-82-PadE4)") (class "Default")
      (node (ref "U3") (pin "E4") (pinfunction "82_E4") (pintype "input"))
    )
    (net (code "103") (name "unconnected-(U3-83-PadE3)") (class "Default")
      (node (ref "U3") (pin "E3") (pinfunction "83_E3") (pintype "input"))
    )
    (net (code "104") (name "unconnected-(U3-84-PadE2)") (class "Default")
      (node (ref "U3") (pin "E2") (pinfunction "84_E2") (pintype "input"))
    )
    (net (code "105") (name "unconnected-(U8-Pad5)") (class "Default")
      (node (ref "U8") (pin "5") (pinfunction "5_5") (pintype "unspecified"))
    )
    (net (code "106") (name "unconnected-(U8-Pad6)") (class "Default")
      (node (ref "U8") (pin "6") (pinfunction "6_6") (pintype "unspecified"))
    )
    (net (code "107") (name "unconnected-(U8-Pad7)") (class "Default")
      (node (ref "U8") (pin "7") (pinfunction "7_7") (pintype "unspecified"))
    )
    (net (code "108") (name "unconnected-(U8-Pad8)") (class "Default")
      (node (ref "U8") (pin "8") (pinfunction "8_8") (pintype "unspecified"))
    )
    (net (code "109") (name "unconnected-(U8-Pad9)") (class "Default")
      (node (ref "U8") (pin "9") (pinfunction "9_9") (pintype "unspecified"))
    )
    (net (code "110") (name "unconnected-(U9-Pad1)") (class "Default")
      (node (ref "U9") (pin "1") (pinfunction "1_1") (pintype "input"))
    )
    (net (code "111") (name "unconnected-(U9-Pad4)") (class "Default")
      (node (ref "U9") (pin "4") (pinfunction "4_4") (pintype "input"))
    )
  )
)
